# TopLevelSchem.net
KiCad netlist of a schematic drawn in Altium Designer
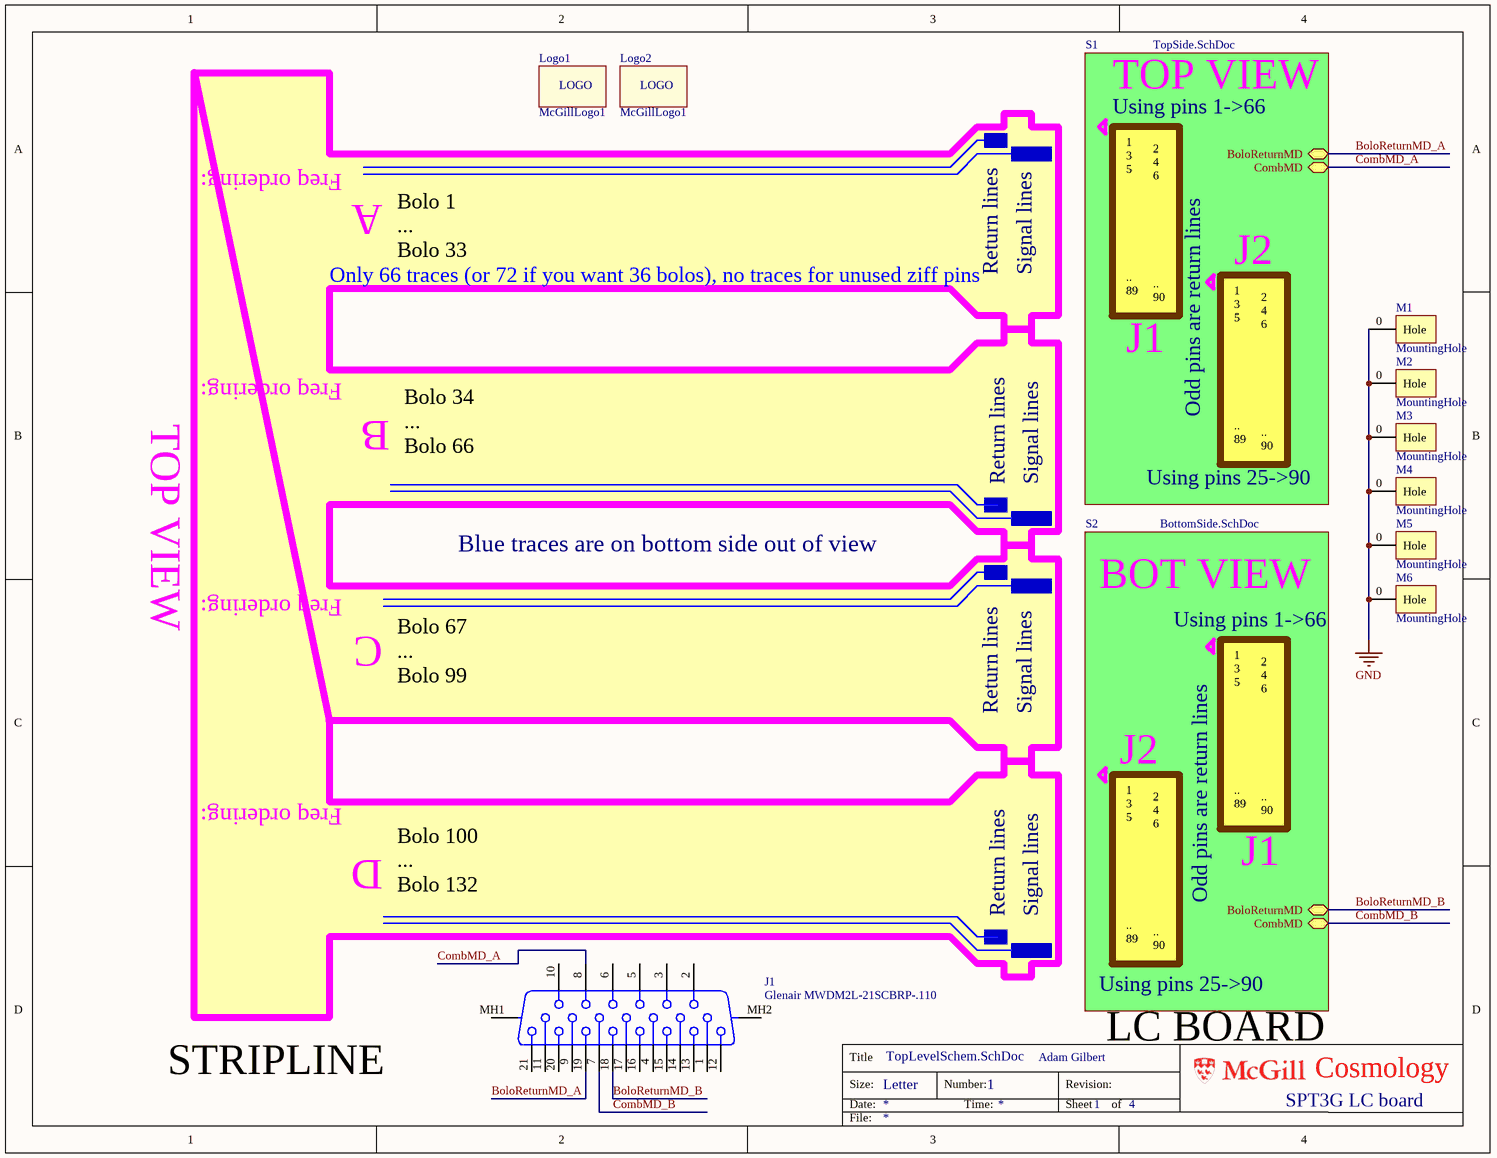
[diagram p0: TopLevelSchem.SchDoc]

(export (version "E")
  (design (tool "Eeschema 10.0.6"))
  (components
    (comp (ref "J1")
      (value "Glenair MWDM2L-21SCBRP-.110")
      (footprint "MWDM2L-21SCBRP-.110")
      (description "Glenair 21pin RA Micro Dsub socket - MWDM2L-21SCBRP-.110")
      (libsource (lib "SPT3G_LCBoard") (part "MWDM2L-21SCBRP-.110"))
    )
    (comp (ref "Logo1")
      (value "McGillLogo1")
      (footprint "McGillLogo1")
      (libsource (lib "SPT3G_LCBoard") (part "Logo"))
    )
    (comp (ref "Logo2")
      (value "McGillLogo1")
      (footprint "McGillLogo1")
      (libsource (lib "SPT3G_LCBoard") (part "Logo"))
    )
    (comp (ref "M1")
      (value "MountingHole")
      (footprint "MountingHole")
      (libsource (lib "SPT3G_LCBoard") (part "MountingHole"))
    )
    (comp (ref "M2")
      (value "MountingHole")
      (footprint "MountingHole")
      (libsource (lib "SPT3G_LCBoard") (part "MountingHole"))
    )
    (comp (ref "M3")
      (value "MountingHole")
      (footprint "MountingHole")
      (libsource (lib "SPT3G_LCBoard") (part "MountingHole"))
    )
    (comp (ref "M4")
      (value "MountingHole")
      (footprint "MountingHole")
      (libsource (lib "SPT3G_LCBoard") (part "MountingHole"))
    )
    (comp (ref "M5")
      (value "MountingHole")
      (footprint "MountingHole")
      (libsource (lib "SPT3G_LCBoard") (part "MountingHole"))
    )
    (comp (ref "M6")
      (value "MountingHole")
      (footprint "MountingHole")
      (libsource (lib "SPT3G_LCBoard") (part "MountingHole"))
    )
  )
  (nets
    (net (code "1") (name "/BoloReturnMD_A") (class "Default")
      (node (ref "J1") (pin "19") (pinfunction "19_19") (pintype "passive"))
    )
    (net (code "2") (name "/BoloReturnMD_B") (class "Default")
      (node (ref "J1") (pin "18") (pinfunction "18_18") (pintype "passive"))
    )
    (net (code "3") (name "/CombMD_A") (class "Default")
      (node (ref "J1") (pin "8") (pinfunction "8_8") (pintype "passive"))
    )
    (net (code "4") (name "/CombMD_B") (class "Default")
      (node (ref "J1") (pin "7") (pinfunction "7_7") (pintype "passive"))
    )
    (net (code "5") (name "GND") (class "Default")
      (node (ref "M1") (pin "0") (pinfunction "Hole_0") (pintype "passive"))
      (node (ref "M2") (pin "0") (pinfunction "Hole_0") (pintype "passive"))
      (node (ref "M3") (pin "0") (pinfunction "Hole_0") (pintype "passive"))
      (node (ref "M4") (pin "0") (pinfunction "Hole_0") (pintype "passive"))
      (node (ref "M5") (pin "0") (pinfunction "Hole_0") (pintype "passive"))
      (node (ref "M6") (pin "0") (pinfunction "Hole_0") (pintype "passive"))
    )
    (net (code "6") (name "unconnected-(J1-Pad1)") (class "Default")
      (node (ref "J1") (pin "1") (pinfunction "1_1") (pintype "passive"))
    )
    (net (code "7") (name "unconnected-(J1-Pad2)") (class "Default")
      (node (ref "J1") (pin "2") (pinfunction "2_2") (pintype "passive"))
    )
    (net (code "8") (name "unconnected-(J1-Pad3)") (class "Default")
      (node (ref "J1") (pin "3") (pinfunction "3_3") (pintype "passive"))
    )
    (net (code "9") (name "unconnected-(J1-Pad4)") (class "Default")
      (node (ref "J1") (pin "4") (pinfunction "4_4") (pintype "passive"))
    )
    (net (code "10") (name "unconnected-(J1-Pad5)") (class "Default")
      (node (ref "J1") (pin "5") (pinfunction "5_5") (pintype "passive"))
    )
    (net (code "11") (name "unconnected-(J1-Pad6)") (class "Default")
      (node (ref "J1") (pin "6") (pinfunction "6_6") (pintype "passive"))
    )
    (net (code "12") (name "unconnected-(J1-Pad9)") (class "Default")
      (node (ref "J1") (pin "9") (pinfunction "9_9") (pintype "passive"))
    )
    (net (code "13") (name "unconnected-(J1-Pad10)") (class "Default")
      (node (ref "J1") (pin "10") (pinfunction "10_10") (pintype "passive"))
    )
    (net (code "14") (name "unconnected-(J1-Pad11)") (class "Default")
      (node (ref "J1") (pin "11") (pinfunction "11_11") (pintype "passive"))
    )
    (net (code "15") (name "unconnected-(J1-Pad12)") (class "Default")
      (node (ref "J1") (pin "12") (pinfunction "12_12") (pintype "passive"))
    )
    (net (code "16") (name "unconnected-(J1-Pad13)") (class "Default")
      (node (ref "J1") (pin "13") (pinfunction "13_13") (pintype "passive"))
    )
    (net (code "17") (name "unconnected-(J1-Pad14)") (class "Default")
      (node (ref "J1") (pin "14") (pinfunction "14_14") (pintype "passive"))
    )
    (net (code "18") (name "unconnected-(J1-Pad15)") (class "Default")
      (node (ref "J1") (pin "15") (pinfunction "15_15") (pintype "passive"))
    )
    (net (code "19") (name "unconnected-(J1-Pad16)") (class "Default")
      (node (ref "J1") (pin "16") (pinfunction "16_16") (pintype "passive"))
    )
    (net (code "20") (name "unconnected-(J1-Pad17)") (class "Default")
      (node (ref "J1") (pin "17") (pinfunction "17_17") (pintype "passive"))
    )
    (net (code "21") (name "unconnected-(J1-Pad20)") (class "Default")
      (node (ref "J1") (pin "20") (pinfunction "20_20") (pintype "passive"))
    )
    (net (code "22") (name "unconnected-(J1-Pad21)") (class "Default")
      (node (ref "J1") (pin "21") (pinfunction "21_21") (pintype "passive"))
    )
    (net (code "23") (name "unconnected-(J1-PadMH1)") (class "Default")
      (node (ref "J1") (pin "MH1") (pinfunction "MH1_MH1") (pintype "passive"))
    )
    (net (code "24") (name "unconnected-(J1-PadMH2)") (class "Default")
      (node (ref "J1") (pin "MH2") (pinfunction "MH2_MH2") (pintype "passive"))
    )
  )
)
